# TWERCC.net
KiCad netlist of a schematic drawn in EAGLE
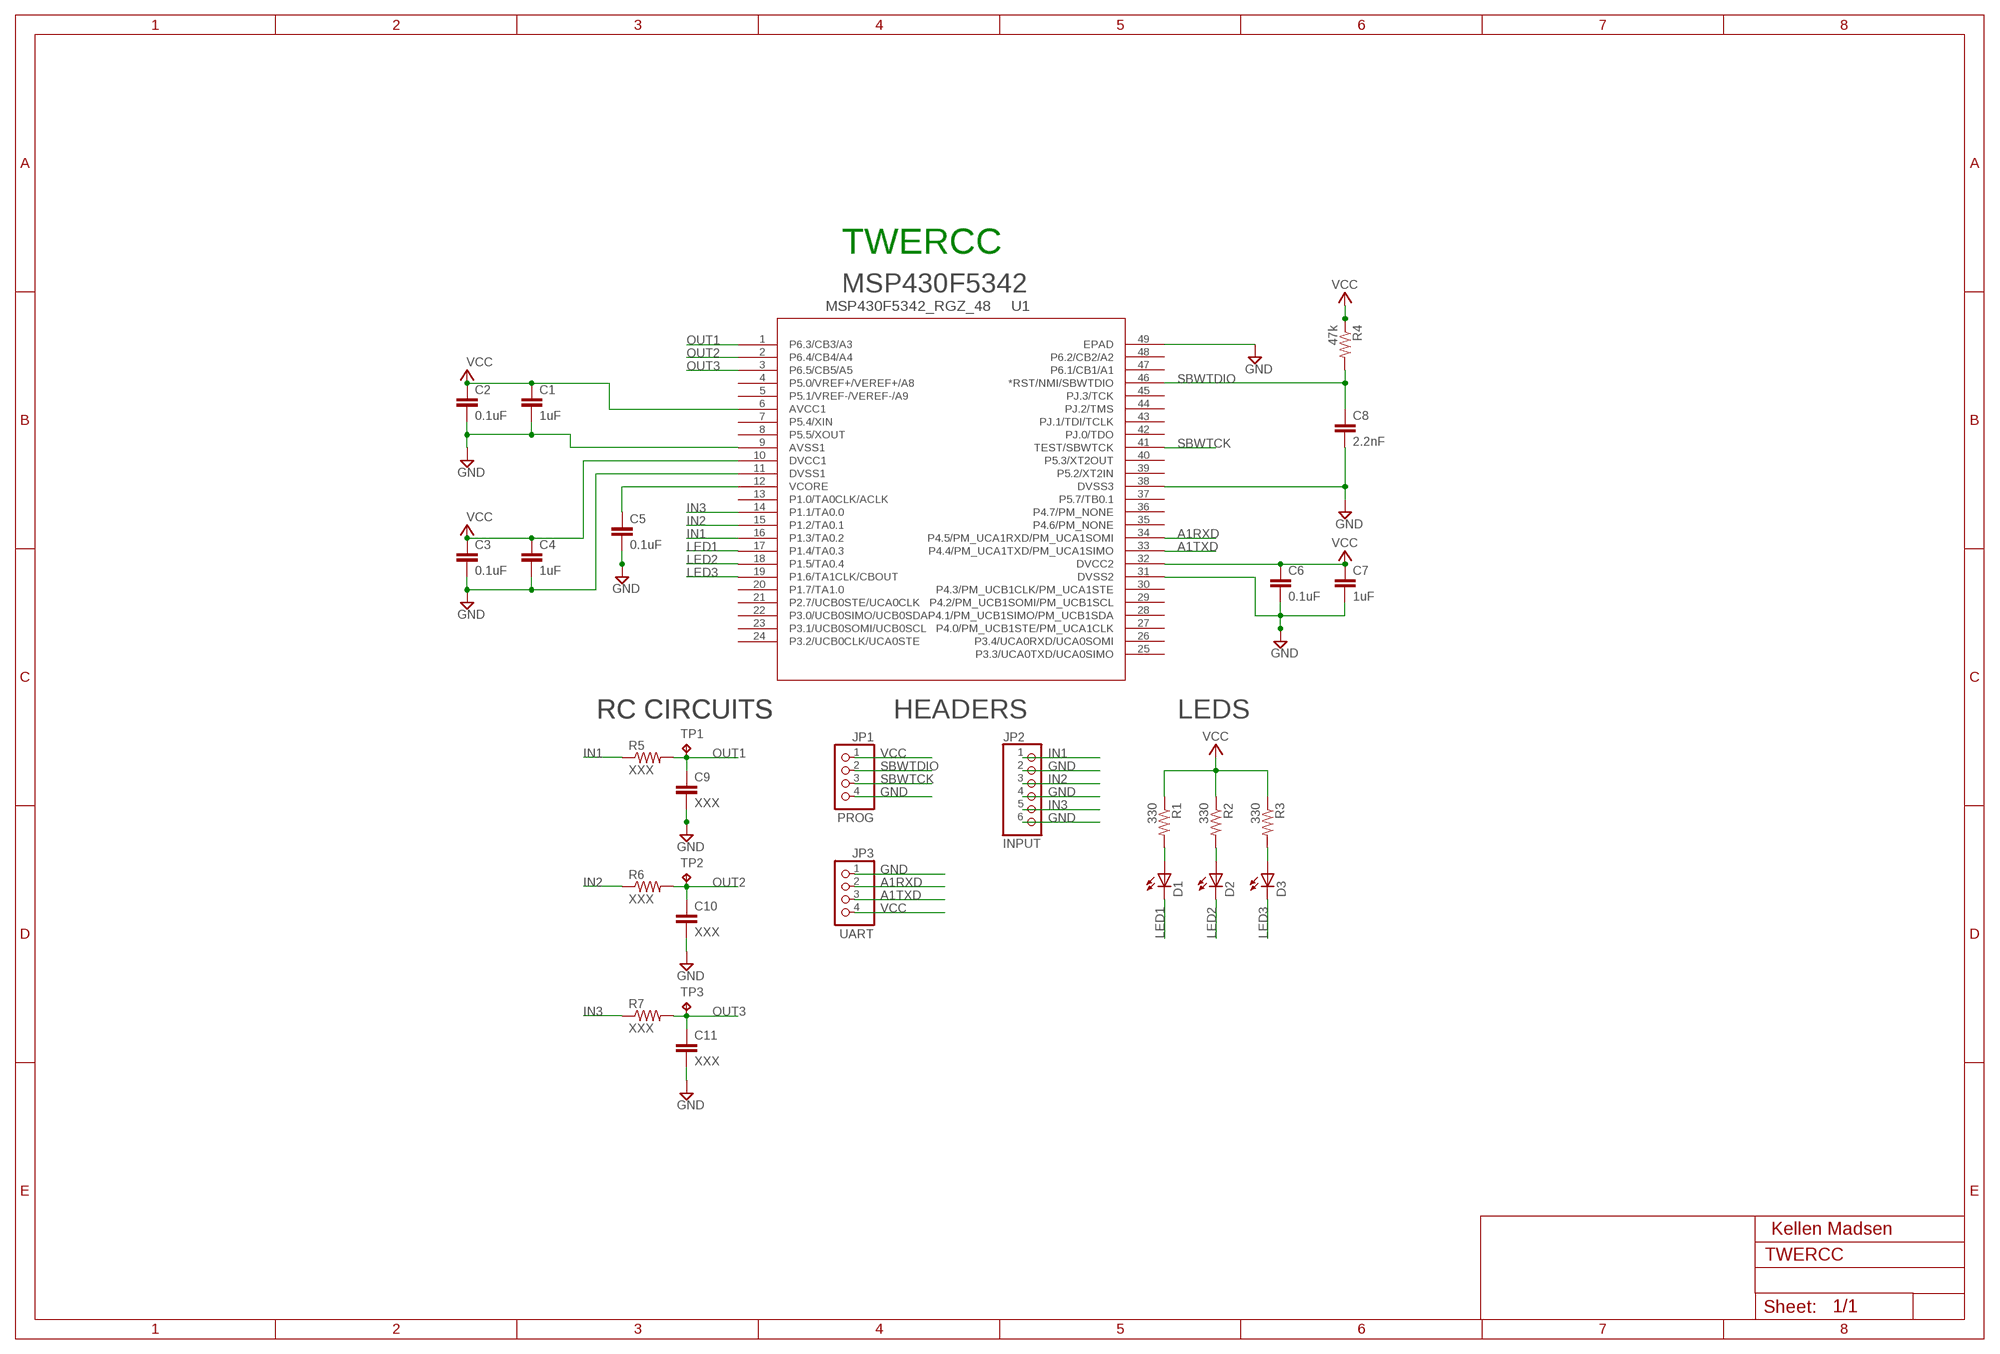
[diagram p0: schematic, sheet 1]

(export (version "E")
  (design (tool "Eeschema 10.0.6"))
  (components
    (comp (ref "C1")
      (value "1uF")
      (footprint "eagle-import:C0603")
      (libsource (lib "eagle-import") (part "C-EUC0603"))
    )
    (comp (ref "C2")
      (value "0.1uF")
      (footprint "eagle-import:C0603")
      (libsource (lib "eagle-import") (part "C-EUC0603"))
    )
    (comp (ref "C3")
      (value "0.1uF")
      (footprint "eagle-import:C0603")
      (libsource (lib "eagle-import") (part "C-EUC0603"))
    )
    (comp (ref "C4")
      (value "1uF")
      (footprint "eagle-import:C0603")
      (libsource (lib "eagle-import") (part "C-EUC0603"))
    )
    (comp (ref "C5")
      (value "0.1uF")
      (footprint "eagle-import:C0603")
      (libsource (lib "eagle-import") (part "C-EUC0603"))
    )
    (comp (ref "C6")
      (value "0.1uF")
      (footprint "eagle-import:C0603")
      (libsource (lib "eagle-import") (part "C-EUC0603"))
    )
    (comp (ref "C7")
      (value "1uF")
      (footprint "eagle-import:C0603")
      (libsource (lib "eagle-import") (part "C-EUC0603"))
    )
    (comp (ref "C8")
      (value "2.2nF")
      (footprint "eagle-import:C0603")
      (libsource (lib "eagle-import") (part "C-EUC0603"))
    )
    (comp (ref "C9")
      (value "XXX")
      (footprint "eagle-import:C0603")
      (libsource (lib "eagle-import") (part "C-EUC0603"))
    )
    (comp (ref "C10")
      (value "XXX")
      (footprint "eagle-import:C0603")
      (libsource (lib "eagle-import") (part "C-EUC0603"))
    )
    (comp (ref "C11")
      (value "XXX")
      (footprint "eagle-import:C0603")
      (libsource (lib "eagle-import") (part "C-EUC0603"))
    )
    (comp (ref "D1")
      (value "LEDCHIPLED_0603")
      (footprint "eagle-import:CHIPLED_0603")
      (libsource (lib "eagle-import") (part "LEDCHIPLED_0603"))
    )
    (comp (ref "D2")
      (value "LEDCHIPLED_0603")
      (footprint "eagle-import:CHIPLED_0603")
      (libsource (lib "eagle-import") (part "LEDCHIPLED_0603"))
    )
    (comp (ref "D3")
      (value "LEDCHIPLED_0603")
      (footprint "eagle-import:CHIPLED_0603")
      (libsource (lib "eagle-import") (part "LEDCHIPLED_0603"))
    )
    (comp (ref "JP1")
      (value "PROG")
      (footprint "eagle-import:1X04")
      (libsource (lib "eagle-import") (part "PINHD-1X4"))
    )
    (comp (ref "JP2")
      (value "INPUT")
      (footprint "eagle-import:1X06")
      (libsource (lib "eagle-import") (part "PINHD-1X6"))
    )
    (comp (ref "JP3")
      (value "UART")
      (footprint "eagle-import:1X04")
      (libsource (lib "eagle-import") (part "PINHD-1X4"))
    )
    (comp (ref "R1")
      (value "330")
      (footprint "eagle-import:R0603")
      (libsource (lib "eagle-import") (part "R-US_R0603"))
    )
    (comp (ref "R2")
      (value "330")
      (footprint "eagle-import:R0603")
      (libsource (lib "eagle-import") (part "R-US_R0603"))
    )
    (comp (ref "R3")
      (value "330")
      (footprint "eagle-import:R0603")
      (libsource (lib "eagle-import") (part "R-US_R0603"))
    )
    (comp (ref "R4")
      (value "47k")
      (footprint "eagle-import:R0603")
      (libsource (lib "eagle-import") (part "R-US_R0603"))
    )
    (comp (ref "R5")
      (value "XXX")
      (footprint "eagle-import:R0603")
      (libsource (lib "eagle-import") (part "R-US_R0603"))
    )
    (comp (ref "R6")
      (value "XXX")
      (footprint "eagle-import:R0603")
      (libsource (lib "eagle-import") (part "R-US_R0603"))
    )
    (comp (ref "R7")
      (value "XXX")
      (footprint "eagle-import:R0603")
      (libsource (lib "eagle-import") (part "R-US_R0603"))
    )
    (comp (ref "TP1")
      (value "TPPAD1-13Y")
      (footprint "eagle-import:P1-13Y")
      (libsource (lib "eagle-import") (part "TPPAD1-13Y"))
    )
    (comp (ref "TP2")
      (value "TPPAD1-13Y")
      (footprint "eagle-import:P1-13Y")
      (libsource (lib "eagle-import") (part "TPPAD1-13Y"))
    )
    (comp (ref "TP3")
      (value "TPPAD1-13Y")
      (footprint "eagle-import:P1-13Y")
      (libsource (lib "eagle-import") (part "TPPAD1-13Y"))
    )
    (comp (ref "U1")
      (value "MSP430F5342_RGZ_48")
      (footprint "eagle-import:RGZ48_5P15X5P15")
      (fields
        (field (name "GENERIC_PART_NUMBER") "MSP430F5342")
        (field (name "MANUFACTURER") "Texas Instruments")
        (field (name "MANUFACTURER_PART_NUMBER") "msp430f5342_rgz_48")
      )
      (libsource (lib "eagle-import") (part "MSP430F5342_RGZ_48"))
    )
  )
  (nets
    (net (code "1") (name "/A1RXD") (class "Default")
      (node (ref "JP3") (pin "2") (pinfunction "2_2") (pintype "passive"))
      (node (ref "U1") (pin "34") (pinfunction "P4.5/PM_UCA1RXD/PM_UCA1SOMI_34") (pintype "bidirectional"))
    )
    (net (code "2") (name "/A1TXD") (class "Default")
      (node (ref "JP3") (pin "3") (pinfunction "3_3") (pintype "passive"))
      (node (ref "U1") (pin "33") (pinfunction "P4.4/PM_UCA1TXD/PM_UCA1SIMO_33") (pintype "bidirectional"))
    )
    (net (code "3") (name "/IN1") (class "Default")
      (node (ref "JP2") (pin "1") (pinfunction "1_1") (pintype "passive"))
      (node (ref "R5") (pin "1") (pinfunction "1_1") (pintype "passive"))
      (node (ref "U1") (pin "16") (pinfunction "P1.3/TA0.2_16") (pintype "bidirectional"))
    )
    (net (code "4") (name "/IN2") (class "Default")
      (node (ref "JP2") (pin "3") (pinfunction "3_3") (pintype "passive"))
      (node (ref "R6") (pin "1") (pinfunction "1_1") (pintype "passive"))
      (node (ref "U1") (pin "15") (pinfunction "P1.2/TA0.1_15") (pintype "bidirectional"))
    )
    (net (code "5") (name "/IN3") (class "Default")
      (node (ref "JP2") (pin "5") (pinfunction "5_5") (pintype "passive"))
      (node (ref "R7") (pin "1") (pinfunction "1_1") (pintype "passive"))
      (node (ref "U1") (pin "14") (pinfunction "P1.1/TA0.0_14") (pintype "bidirectional"))
    )
    (net (code "6") (name "/LED1") (class "Default")
      (node (ref "D1") (pin "C") (pinfunction "C_C") (pintype "passive"))
      (node (ref "U1") (pin "17") (pinfunction "P1.4/TA0.3_17") (pintype "bidirectional"))
    )
    (net (code "7") (name "/LED2") (class "Default")
      (node (ref "D2") (pin "C") (pinfunction "C_C") (pintype "passive"))
      (node (ref "U1") (pin "18") (pinfunction "P1.5/TA0.4_18") (pintype "bidirectional"))
    )
    (net (code "8") (name "/LED3") (class "Default")
      (node (ref "D3") (pin "C") (pinfunction "C_C") (pintype "passive"))
      (node (ref "U1") (pin "19") (pinfunction "P1.6/TA1CLK/CBOUT_19") (pintype "bidirectional"))
    )
    (net (code "9") (name "/OUT1") (class "Default")
      (node (ref "C9") (pin "1") (pinfunction "1_1") (pintype "passive"))
      (node (ref "R5") (pin "2") (pinfunction "2_2") (pintype "passive"))
      (node (ref "TP1") (pin "TP") (pinfunction "TP_TP") (pintype "input"))
      (node (ref "U1") (pin "1") (pinfunction "P6.3/CB3/A3_1") (pintype "bidirectional"))
    )
    (net (code "10") (name "/OUT2") (class "Default")
      (node (ref "C10") (pin "1") (pinfunction "1_1") (pintype "passive"))
      (node (ref "R6") (pin "2") (pinfunction "2_2") (pintype "passive"))
      (node (ref "TP2") (pin "TP") (pinfunction "TP_TP") (pintype "input"))
      (node (ref "U1") (pin "2") (pinfunction "P6.4/CB4/A4_2") (pintype "bidirectional"))
    )
    (net (code "11") (name "/OUT3") (class "Default")
      (node (ref "C11") (pin "1") (pinfunction "1_1") (pintype "passive"))
      (node (ref "R7") (pin "2") (pinfunction "2_2") (pintype "passive"))
      (node (ref "TP3") (pin "TP") (pinfunction "TP_TP") (pintype "input"))
      (node (ref "U1") (pin "3") (pinfunction "P6.5/CB5/A5_3") (pintype "bidirectional"))
    )
    (net (code "12") (name "/SBWTCK") (class "Default")
      (node (ref "JP1") (pin "3") (pinfunction "3_3") (pintype "passive"))
      (node (ref "U1") (pin "41") (pinfunction "TEST/SBWTCK_41") (pintype "bidirectional"))
    )
    (net (code "13") (name "/SBWTDIO") (class "Default")
      (node (ref "C8") (pin "1") (pinfunction "1_1") (pintype "passive"))
      (node (ref "JP1") (pin "2") (pinfunction "2_2") (pintype "passive"))
      (node (ref "R4") (pin "2") (pinfunction "2_2") (pintype "passive"))
      (node (ref "U1") (pin "46") (pinfunction "*RST/NMI/SBWTDIO_46") (pintype "bidirectional"))
    )
    (net (code "14") (name "GND") (class "Default")
      (node (ref "C1") (pin "2") (pinfunction "2_2") (pintype "passive"))
      (node (ref "C10") (pin "2") (pinfunction "2_2") (pintype "passive"))
      (node (ref "C11") (pin "2") (pinfunction "2_2") (pintype "passive"))
      (node (ref "C2") (pin "2") (pinfunction "2_2") (pintype "passive"))
      (node (ref "C3") (pin "2") (pinfunction "2_2") (pintype "passive"))
      (node (ref "C4") (pin "2") (pinfunction "2_2") (pintype "passive"))
      (node (ref "C5") (pin "2") (pinfunction "2_2") (pintype "passive"))
      (node (ref "C6") (pin "2") (pinfunction "2_2") (pintype "passive"))
      (node (ref "C7") (pin "2") (pinfunction "2_2") (pintype "passive"))
      (node (ref "C8") (pin "2") (pinfunction "2_2") (pintype "passive"))
      (node (ref "C9") (pin "2") (pinfunction "2_2") (pintype "passive"))
      (node (ref "JP1") (pin "4") (pinfunction "4_4") (pintype "passive"))
      (node (ref "JP2") (pin "2") (pinfunction "2_2") (pintype "passive"))
      (node (ref "JP2") (pin "4") (pinfunction "4_4") (pintype "passive"))
      (node (ref "JP2") (pin "6") (pinfunction "6_6") (pintype "passive"))
      (node (ref "JP3") (pin "1") (pinfunction "1_1") (pintype "passive"))
      (node (ref "U1") (pin "11") (pinfunction "DVSS1_11") (pintype "power_in"))
      (node (ref "U1") (pin "31") (pinfunction "DVSS2_31") (pintype "power_in"))
      (node (ref "U1") (pin "38") (pinfunction "DVSS3_38") (pintype "power_in"))
      (node (ref "U1") (pin "49") (pinfunction "EPAD_49") (pintype "passive"))
      (node (ref "U1") (pin "9") (pinfunction "AVSS1_9") (pintype "power_in"))
    )
    (net (code "15") (name "Net-(D1-PadA)") (class "Default")
      (node (ref "D1") (pin "A") (pinfunction "A_A") (pintype "passive"))
      (node (ref "R1") (pin "2") (pinfunction "2_2") (pintype "passive"))
    )
    (net (code "16") (name "Net-(D2-PadA)") (class "Default")
      (node (ref "D2") (pin "A") (pinfunction "A_A") (pintype "passive"))
      (node (ref "R2") (pin "2") (pinfunction "2_2") (pintype "passive"))
    )
    (net (code "17") (name "Net-(D3-PadA)") (class "Default")
      (node (ref "D3") (pin "A") (pinfunction "A_A") (pintype "passive"))
      (node (ref "R3") (pin "2") (pinfunction "2_2") (pintype "passive"))
    )
    (net (code "18") (name "Net-(U1-VCORE)") (class "Default")
      (node (ref "C5") (pin "1") (pinfunction "1_1") (pintype "passive"))
      (node (ref "U1") (pin "12") (pinfunction "VCORE_12") (pintype "power_in"))
    )
    (net (code "19") (name "VCC") (class "Default")
      (node (ref "C1") (pin "1") (pinfunction "1_1") (pintype "passive"))
      (node (ref "C2") (pin "1") (pinfunction "1_1") (pintype "passive"))
      (node (ref "C3") (pin "1") (pinfunction "1_1") (pintype "passive"))
      (node (ref "C4") (pin "1") (pinfunction "1_1") (pintype "passive"))
      (node (ref "C6") (pin "1") (pinfunction "1_1") (pintype "passive"))
      (node (ref "C7") (pin "1") (pinfunction "1_1") (pintype "passive"))
      (node (ref "JP1") (pin "1") (pinfunction "1_1") (pintype "passive"))
      (node (ref "JP3") (pin "4") (pinfunction "4_4") (pintype "passive"))
      (node (ref "R1") (pin "1") (pinfunction "1_1") (pintype "passive"))
      (node (ref "R2") (pin "1") (pinfunction "1_1") (pintype "passive"))
      (node (ref "R3") (pin "1") (pinfunction "1_1") (pintype "passive"))
      (node (ref "R4") (pin "1") (pinfunction "1_1") (pintype "passive"))
      (node (ref "U1") (pin "10") (pinfunction "DVCC1_10") (pintype "power_in"))
      (node (ref "U1") (pin "32") (pinfunction "DVCC2_32") (pintype "power_in"))
      (node (ref "U1") (pin "6") (pinfunction "AVCC1_6") (pintype "power_in"))
    )
    (net (code "20") (name "unconnected-(U1-P1.0{slash}TA0CLK{slash}ACLK-Pad13)") (class "Default")
      (node (ref "U1") (pin "13") (pinfunction "P1.0/TA0CLK/ACLK_13") (pintype "bidirectional"))
    )
    (net (code "21") (name "unconnected-(U1-P1.7{slash}TA1.0-Pad20)") (class "Default")
      (node (ref "U1") (pin "20") (pinfunction "P1.7/TA1.0_20") (pintype "bidirectional"))
    )
    (net (code "22") (name "unconnected-(U1-P2.7{slash}UCB0STE{slash}UCA0CLK-Pad21)") (class "Default")
      (node (ref "U1") (pin "21") (pinfunction "P2.7/UCB0STE/UCA0CLK_21") (pintype "bidirectional"))
    )
    (net (code "23") (name "unconnected-(U1-P3.0{slash}UCB0SIMO{slash}UCB0SDA-Pad22)") (class "Default")
      (node (ref "U1") (pin "22") (pinfunction "P3.0/UCB0SIMO/UCB0SDA_22") (pintype "bidirectional"))
    )
    (net (code "24") (name "unconnected-(U1-P3.1{slash}UCB0SOMI{slash}UCB0SCL-Pad23)") (class "Default")
      (node (ref "U1") (pin "23") (pinfunction "P3.1/UCB0SOMI/UCB0SCL_23") (pintype "bidirectional"))
    )
    (net (code "25") (name "unconnected-(U1-P3.2{slash}UCB0CLK{slash}UCA0STE-Pad24)") (class "Default")
      (node (ref "U1") (pin "24") (pinfunction "P3.2/UCB0CLK/UCA0STE_24") (pintype "bidirectional"))
    )
    (net (code "26") (name "unconnected-(U1-P3.3{slash}UCA0TXD{slash}UCA0SIMO-Pad25)") (class "Default")
      (node (ref "U1") (pin "25") (pinfunction "P3.3/UCA0TXD/UCA0SIMO_25") (pintype "bidirectional"))
    )
    (net (code "27") (name "unconnected-(U1-P3.4{slash}UCA0RXD{slash}UCA0SOMI-Pad26)") (class "Default")
      (node (ref "U1") (pin "26") (pinfunction "P3.4/UCA0RXD/UCA0SOMI_26") (pintype "bidirectional"))
    )
    (net (code "28") (name "unconnected-(U1-P4.0{slash}PM_UCB1STE{slash}PM_UCA1CLK-Pad27)") (class "Default")
      (node (ref "U1") (pin "27") (pinfunction "P4.0/PM_UCB1STE/PM_UCA1CLK_27") (pintype "bidirectional"))
    )
    (net (code "29") (name "unconnected-(U1-P4.1{slash}PM_UCB1SIMO{slash}PM_UCB1SDA-Pad28)") (class "Default")
      (node (ref "U1") (pin "28") (pinfunction "P4.1/PM_UCB1SIMO/PM_UCB1SDA_28") (pintype "bidirectional"))
    )
    (net (code "30") (name "unconnected-(U1-P4.2{slash}PM_UCB1SOMI{slash}PM_UCB1SCL-Pad29)") (class "Default")
      (node (ref "U1") (pin "29") (pinfunction "P4.2/PM_UCB1SOMI/PM_UCB1SCL_29") (pintype "bidirectional"))
    )
    (net (code "31") (name "unconnected-(U1-P4.3{slash}PM_UCB1CLK{slash}PM_UCA1STE-Pad30)") (class "Default")
      (node (ref "U1") (pin "30") (pinfunction "P4.3/PM_UCB1CLK/PM_UCA1STE_30") (pintype "bidirectional"))
    )
    (net (code "32") (name "unconnected-(U1-P4.6{slash}PM_NONE-Pad35)") (class "Default")
      (node (ref "U1") (pin "35") (pinfunction "P4.6/PM_NONE_35") (pintype "bidirectional"))
    )
    (net (code "33") (name "unconnected-(U1-P4.7{slash}PM_NONE-Pad36)") (class "Default")
      (node (ref "U1") (pin "36") (pinfunction "P4.7/PM_NONE_36") (pintype "bidirectional"))
    )
    (net (code "34") (name "unconnected-(U1-P5.0{slash}VREF+{slash}VEREF+{slash}A8-Pad4)") (class "Default")
      (node (ref "U1") (pin "4") (pinfunction "P5.0/VREF+/VEREF+/A8_4") (pintype "bidirectional"))
    )
    (net (code "35") (name "unconnected-(U1-P5.1{slash}VREF-{slash}VEREF-{slash}A9-Pad5)") (class "Default")
      (node (ref "U1") (pin "5") (pinfunction "P5.1/VREF-/VEREF-/A9_5") (pintype "bidirectional"))
    )
    (net (code "36") (name "unconnected-(U1-P5.2{slash}XT2IN-Pad39)") (class "Default")
      (node (ref "U1") (pin "39") (pinfunction "P5.2/XT2IN_39") (pintype "bidirectional"))
    )
    (net (code "37") (name "unconnected-(U1-P5.3{slash}XT2OUT-Pad40)") (class "Default")
      (node (ref "U1") (pin "40") (pinfunction "P5.3/XT2OUT_40") (pintype "bidirectional"))
    )
    (net (code "38") (name "unconnected-(U1-P5.4{slash}XIN-Pad7)") (class "Default")
      (node (ref "U1") (pin "7") (pinfunction "P5.4/XIN_7") (pintype "bidirectional"))
    )
    (net (code "39") (name "unconnected-(U1-P5.5{slash}XOUT-Pad8)") (class "Default")
      (node (ref "U1") (pin "8") (pinfunction "P5.5/XOUT_8") (pintype "bidirectional"))
    )
    (net (code "40") (name "unconnected-(U1-P5.7{slash}TB0.1-Pad37)") (class "Default")
      (node (ref "U1") (pin "37") (pinfunction "P5.7/TB0.1_37") (pintype "bidirectional"))
    )
    (net (code "41") (name "unconnected-(U1-P6.1{slash}CB1{slash}A1-Pad47)") (class "Default")
      (node (ref "U1") (pin "47") (pinfunction "P6.1/CB1/A1_47") (pintype "bidirectional"))
    )
    (net (code "42") (name "unconnected-(U1-P6.2{slash}CB2{slash}A2-Pad48)") (class "Default")
      (node (ref "U1") (pin "48") (pinfunction "P6.2/CB2/A2_48") (pintype "bidirectional"))
    )
    (net (code "43") (name "unconnected-(U1-PJ.0{slash}TDO-Pad42)") (class "Default")
      (node (ref "U1") (pin "42") (pinfunction "PJ.0/TDO_42") (pintype "bidirectional"))
    )
    (net (code "44") (name "unconnected-(U1-PJ.1{slash}TDI{slash}TCLK-Pad43)") (class "Default")
      (node (ref "U1") (pin "43") (pinfunction "PJ.1/TDI/TCLK_43") (pintype "bidirectional"))
    )
    (net (code "45") (name "unconnected-(U1-PJ.2{slash}TMS-Pad44)") (class "Default")
      (node (ref "U1") (pin "44") (pinfunction "PJ.2/TMS_44") (pintype "bidirectional"))
    )
    (net (code "46") (name "unconnected-(U1-PJ.3{slash}TCK-Pad45)") (class "Default")
      (node (ref "U1") (pin "45") (pinfunction "PJ.3/TCK_45") (pintype "bidirectional"))
    )
  )
)
